# ESIMA_E-Meter_CPU.net
KiCad netlist of a schematic drawn in Altium Designer
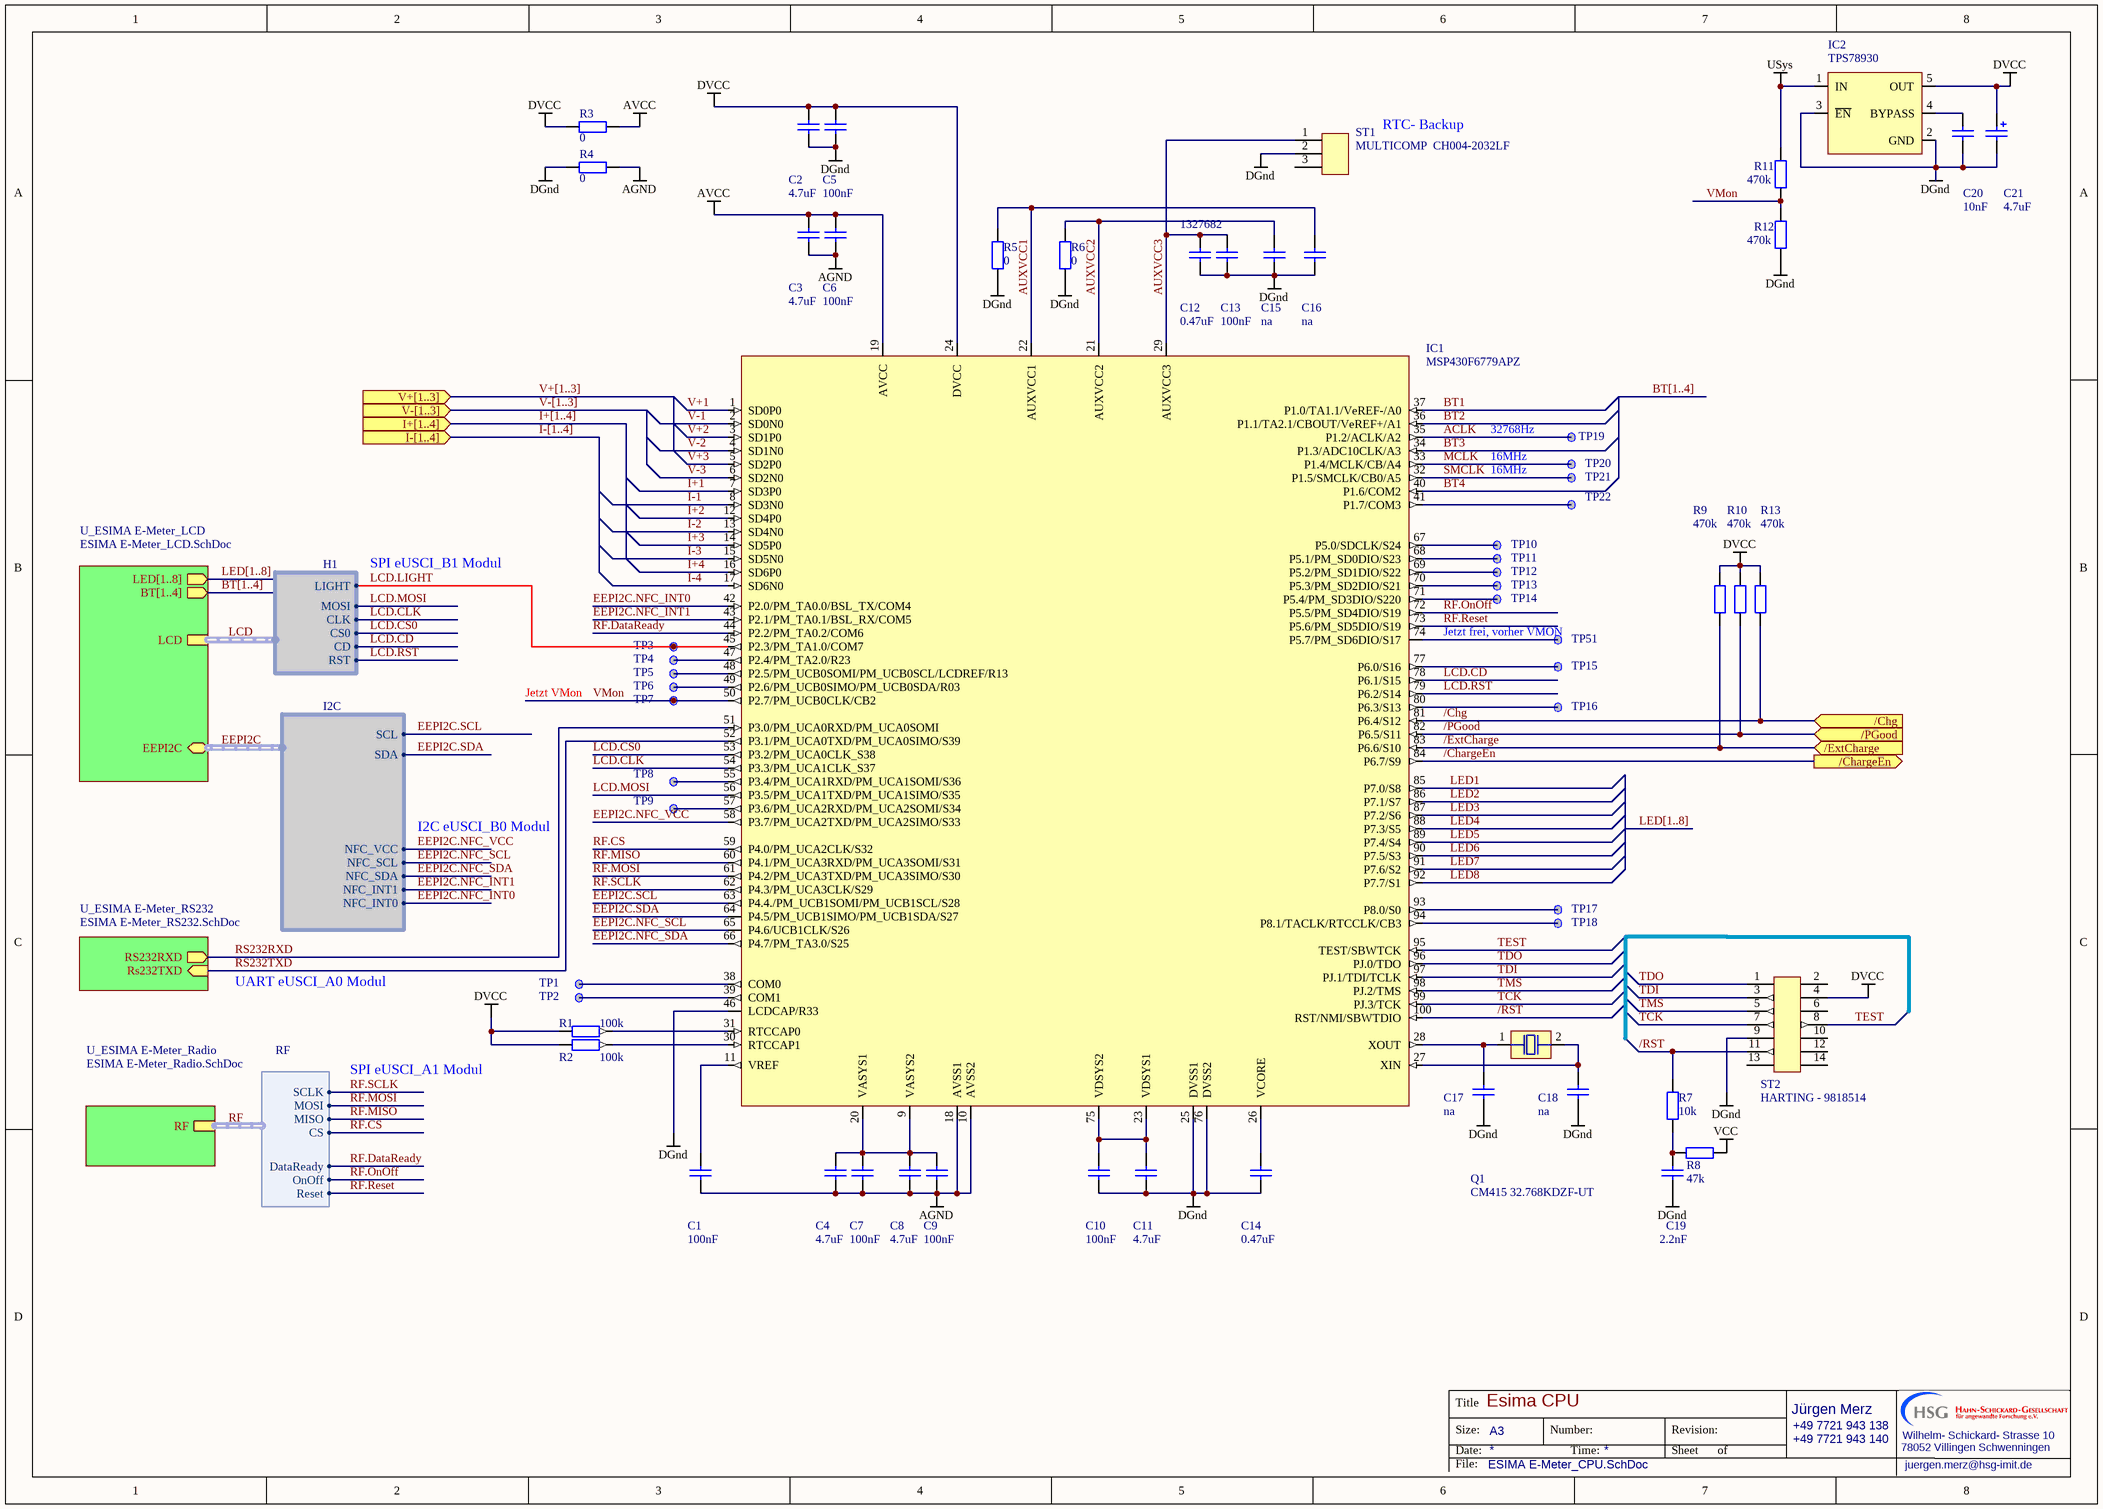
[diagram p0: ESIMA E-Meter_CPU.SchDoc]

(export (version "E")
  (design (tool "Eeschema 10.0.6"))
  (components
    (comp (ref "C1")
      (value "100nF")
      (footprint "CAPC1608N")
      (description "CAPC1608 (C0603)")
      (libsource (lib "JM_Kondensatoren") (part "CAPC1608 (C0603)"))
    )
    (comp (ref "C2")
      (value "4.7uF")
      (footprint "CAPC1608N")
      (description "CAPC1608 (C0603)")
      (libsource (lib "JM_Kondensatoren") (part "CAPC1608 (C0603)"))
    )
    (comp (ref "C3")
      (value "4.7uF")
      (footprint "CAPC1608N")
      (description "CAPC1608 (C0603)")
      (libsource (lib "JM_Kondensatoren") (part "CAPC1608 (C0603)"))
    )
    (comp (ref "C4")
      (value "4.7uF")
      (footprint "CAPC1608N")
      (description "CAPC1608 (C0603)")
      (libsource (lib "JM_Kondensatoren") (part "CAPC1608 (C0603)"))
    )
    (comp (ref "C5")
      (value "100nF")
      (footprint "CAPC1608N")
      (description "CAPC1608 (C0603)")
      (libsource (lib "JM_Kondensatoren") (part "CAPC1608 (C0603)"))
    )
    (comp (ref "C6")
      (value "100nF")
      (footprint "CAPC1608N")
      (description "CAPC1608 (C0603)")
      (libsource (lib "JM_Kondensatoren") (part "CAPC1608 (C0603)"))
    )
    (comp (ref "C7")
      (value "100nF")
      (footprint "CAPC1608N")
      (description "CAPC1608 (C0603)")
      (libsource (lib "JM_Kondensatoren") (part "CAPC1608 (C0603)"))
    )
    (comp (ref "C8")
      (value "4.7uF")
      (footprint "CAPC1608N")
      (description "CAPC1608 (C0603)")
      (libsource (lib "JM_Kondensatoren") (part "CAPC1608 (C0603)"))
    )
    (comp (ref "C9")
      (value "100nF")
      (footprint "CAPC1608N")
      (description "CAPC1608 (C0603)")
      (libsource (lib "JM_Kondensatoren") (part "CAPC1608 (C0603)"))
    )
    (comp (ref "C10")
      (value "100nF")
      (footprint "CAPC1608N")
      (description "CAPC1608 (C0603)")
      (libsource (lib "JM_Kondensatoren") (part "CAPC1608 (C0603)"))
    )
    (comp (ref "C11")
      (value "4.7uF")
      (footprint "CAPC1608N")
      (description "CAPC1608 (C0603)")
      (libsource (lib "JM_Kondensatoren") (part "CAPC1608 (C0603)"))
    )
    (comp (ref "C12")
      (value "0.47uF")
      (footprint "CAPC1608N")
      (description "CAPC1608 (C0603)")
      (fields (field (name "SUPPLIER PART NUMBER 1") "1327682"))
      (libsource (lib "JM_Kondensatoren") (part "CAPC1608 (C0603)"))
    )
    (comp (ref "C13")
      (value "100nF")
      (footprint "CAPC1608N")
      (description "CAPC1608 (C0603)")
      (libsource (lib "JM_Kondensatoren") (part "CAPC1608 (C0603)"))
    )
    (comp (ref "C14")
      (value "0.47uF")
      (footprint "CAPC1608N")
      (description "CAPC1608 (C0603)")
      (libsource (lib "JM_Kondensatoren") (part "CAPC1608 (C0603)"))
    )
    (comp (ref "C15")
      (value "na")
      (footprint "CAPC1608N")
      (description "CAPC1608 (C0603)")
      (libsource (lib "JM_Kondensatoren") (part "CAPC1608 (C0603)"))
    )
    (comp (ref "C16")
      (value "na")
      (footprint "CAPC1608N")
      (description "CAPC1608 (C0603)")
      (libsource (lib "JM_Kondensatoren") (part "CAPC1608 (C0603)"))
    )
    (comp (ref "C17")
      (value "na")
      (footprint "CAPC1608N")
      (description "CAPC1608 (C0603)")
      (libsource (lib "JM_Kondensatoren") (part "CAPC1608 (C0603)"))
    )
    (comp (ref "C18")
      (value "na")
      (footprint "CAPC1608N")
      (description "CAPC1608 (C0603)")
      (libsource (lib "JM_Kondensatoren") (part "CAPC1608 (C0603)"))
    )
    (comp (ref "C19")
      (value "2.2nF")
      (footprint "CAPC1608N")
      (description "CAPC1608 (C0603)")
      (libsource (lib "JM_Kondensatoren") (part "CAPC1608 (C0603)"))
    )
    (comp (ref "C20")
      (value "10nF")
      (footprint "CAPC1608N")
      (description "CAPC1608 (C0603)")
      (libsource (lib "JM_Kondensatoren") (part "CAPC1608 (C0603)"))
    )
    (comp (ref "C21")
      (value "4.7uF")
      (footprint "Cap Tant Pol Form B")
      (libsource (lib "JM_Kondensatoren") (part "Cap Tant Pol Form B"))
    )
    (comp (ref "IC1")
      (value "MSP430F6779APZ")
      (footprint "TI-PZ100_N")
      (description "Mikroprozessor 16bit Polyphase Metering")
      (libsource (lib "JM_Halbleiter") (part "MSP430F6779AIPZ"))
    )
    (comp (ref "IC2")
      (value "TPS78930")
      (footprint "TI-DBV5 (SOT23-5)")
      (description "Voltageregulator low Current")
      (libsource (lib "HSG-IMIT_JuergenMerz") (part "TPS78930"))
    )
    (comp (ref "Q1")
      (value "CM415 32.768KDZF-UT")
      (footprint "Quarz 2 Pin 4.1mm * 1.5mm")
      (description "Quarz 2 Pin 4.1mm * 1.5mm")
      (libsource (lib "JM_Kondensatoren") (part "Quarz 2 Pin 4.1mm * 1.5mm"))
    )
    (comp (ref "R1")
      (value "100k")
      (footprint "RESC1608N")
      (description "RESC1608 (R0603)")
      (libsource (lib "JM_Widerstaende") (part "RESC1608 (R0603)"))
    )
    (comp (ref "R2")
      (value "100k")
      (footprint "RESC1608N")
      (description "RESC1608 (R0603)")
      (libsource (lib "JM_Widerstaende") (part "RESC1608 (R0603)"))
    )
    (comp (ref "R3")
      (value "0")
      (footprint "RESC2012N")
      (description "RESC2012N (R0805)")
      (libsource (lib "JM_Widerstaende") (part "RESC2012N (R0805)"))
    )
    (comp (ref "R4")
      (value "0")
      (footprint "RESC2012N")
      (description "RESC2012N (R0805)")
      (libsource (lib "JM_Widerstaende") (part "RESC2012N (R0805)"))
    )
    (comp (ref "R5")
      (value "0")
      (footprint "RESC1608N")
      (description "RESC1608 (R0603)")
      (libsource (lib "") (part "RESC1608 (R0603)_1"))
    )
    (comp (ref "R6")
      (value "0")
      (footprint "RESC1608N")
      (description "RESC1608 (R0603)")
      (libsource (lib "") (part "RESC1608 (R0603)_1"))
    )
    (comp (ref "R7")
      (value "10k")
      (footprint "RESC1608N")
      (description "RESC1608 (R0603)")
      (libsource (lib "") (part "RESC1608 (R0603)_2"))
    )
    (comp (ref "R8")
      (value "47k")
      (footprint "RESC1608N")
      (description "RESC1608 (R0603)")
      (libsource (lib "JM_Widerstaende") (part "RESC1608 (R0603)"))
    )
    (comp (ref "R9")
      (value "470k")
      (footprint "RESC1608N")
      (description "RESC1608 (R0603)")
      (libsource (lib "JM_Widerstaende") (part "RESC1608 (R0603)"))
    )
    (comp (ref "R10")
      (value "470k")
      (footprint "RESC1608N")
      (description "RESC1608 (R0603)")
      (libsource (lib "JM_Widerstaende") (part "RESC1608 (R0603)"))
    )
    (comp (ref "R11")
      (value "470k")
      (footprint "RESC1608N")
      (description "RESC1608 (R0603)")
      (libsource (lib "") (part "RESC1608 (R0603)_1"))
    )
    (comp (ref "R12")
      (value "470k")
      (footprint "RESC1608N")
      (description "RESC1608 (R0603)")
      (libsource (lib "") (part "RESC1608 (R0603)_1"))
    )
    (comp (ref "R13")
      (value "470k")
      (footprint "RESC1608N")
      (description "RESC1608 (R0603)")
      (libsource (lib "JM_Widerstaende") (part "RESC1608 (R0603)"))
    )
    (comp (ref "ST1")
      (value "MULTICOMP  CH004-2032LF")
      (footprint "MULTICOMP  CH004-2032LF")
      (description "Stecker 3Pol universal")
      (libsource (lib "HSG-IMIT_JuergenMerz") (part "Stecker 3Pol universal"))
    )
    (comp (ref "ST2")
      (value "HARTING - 9818514")
      (footprint "HARTING -09 18 514 7324")
      (description "Messerleiste Gerade 14Pol")
      (libsource (lib "JM_Elektromechanik") (part "HARTING - 9818514"))
    )
    (comp (ref "TP1")
      (value "Testpoint 1mm")
      (footprint "Testpoint 1mm")
      (libsource (lib "HSG-IMIT_JuergenMerz") (part "Tespoint 1mm"))
    )
    (comp (ref "TP2")
      (value "Testpoint 1mm")
      (footprint "Testpoint 1mm")
      (libsource (lib "HSG-IMIT_JuergenMerz") (part "Tespoint 1mm"))
    )
    (comp (ref "TP3")
      (value "Testpoint 1mm")
      (footprint "Testpoint 1mm")
      (libsource (lib "HSG-IMIT_JuergenMerz") (part "Tespoint 1mm"))
    )
    (comp (ref "TP4")
      (value "Testpoint 1mm")
      (footprint "Testpoint 1mm")
      (libsource (lib "HSG-IMIT_JuergenMerz") (part "Tespoint 1mm"))
    )
    (comp (ref "TP5")
      (value "Testpoint 1mm")
      (footprint "Testpoint 1mm")
      (libsource (lib "HSG-IMIT_JuergenMerz") (part "Tespoint 1mm"))
    )
    (comp (ref "TP6")
      (value "Testpoint 1mm")
      (footprint "Testpoint 1mm")
      (libsource (lib "HSG-IMIT_JuergenMerz") (part "Tespoint 1mm"))
    )
    (comp (ref "TP7")
      (value "Testpoint 1mm")
      (footprint "Testpoint 1mm")
      (libsource (lib "HSG-IMIT_JuergenMerz") (part "Tespoint 1mm"))
    )
    (comp (ref "TP8")
      (value "Testpoint 1mm")
      (footprint "Testpoint 1mm")
      (libsource (lib "HSG-IMIT_JuergenMerz") (part "Tespoint 1mm"))
    )
    (comp (ref "TP9")
      (value "Testpoint 1mm")
      (footprint "Testpoint 1mm")
      (libsource (lib "HSG-IMIT_JuergenMerz") (part "Tespoint 1mm"))
    )
    (comp (ref "TP10")
      (value "Testpoint 1mm")
      (footprint "Testpoint 1mm")
      (libsource (lib "HSG-IMIT_JuergenMerz") (part "Tespoint 1mm"))
    )
    (comp (ref "TP11")
      (value "Testpoint 1mm")
      (footprint "Testpoint 1mm")
      (libsource (lib "HSG-IMIT_JuergenMerz") (part "Tespoint 1mm"))
    )
    (comp (ref "TP12")
      (value "Testpoint 1mm")
      (footprint "Testpoint 1mm")
      (libsource (lib "HSG-IMIT_JuergenMerz") (part "Tespoint 1mm"))
    )
    (comp (ref "TP13")
      (value "Testpoint 1mm")
      (footprint "Testpoint 1mm")
      (libsource (lib "HSG-IMIT_JuergenMerz") (part "Tespoint 1mm"))
    )
    (comp (ref "TP14")
      (value "Testpoint 1mm")
      (footprint "Testpoint 1mm")
      (libsource (lib "HSG-IMIT_JuergenMerz") (part "Tespoint 1mm"))
    )
    (comp (ref "TP15")
      (value "Testpoint 1mm")
      (footprint "Testpoint 1mm")
      (libsource (lib "HSG-IMIT_JuergenMerz") (part "Tespoint 1mm"))
    )
    (comp (ref "TP16")
      (value "Testpoint 1mm")
      (footprint "Testpoint 1mm")
      (libsource (lib "HSG-IMIT_JuergenMerz") (part "Tespoint 1mm"))
    )
    (comp (ref "TP17")
      (value "Testpoint 1mm")
      (footprint "Testpoint 1mm")
      (libsource (lib "HSG-IMIT_JuergenMerz") (part "Tespoint 1mm"))
    )
    (comp (ref "TP18")
      (value "Testpoint 1mm")
      (footprint "Testpoint 1mm")
      (libsource (lib "HSG-IMIT_JuergenMerz") (part "Tespoint 1mm"))
    )
    (comp (ref "TP19")
      (value "Testpoint 1mm")
      (footprint "Testpoint 1mm")
      (libsource (lib "HSG-IMIT_JuergenMerz") (part "Tespoint 1mm"))
    )
    (comp (ref "TP20")
      (value "Testpoint 1mm")
      (footprint "Testpoint 1mm")
      (libsource (lib "HSG-IMIT_JuergenMerz") (part "Tespoint 1mm"))
    )
    (comp (ref "TP21")
      (value "Testpoint 1mm")
      (footprint "Testpoint 1mm")
      (libsource (lib "HSG-IMIT_JuergenMerz") (part "Tespoint 1mm"))
    )
    (comp (ref "TP22")
      (value "Testpoint 1mm")
      (footprint "Testpoint 1mm")
      (libsource (lib "HSG-IMIT_JuergenMerz") (part "Tespoint 1mm"))
    )
    (comp (ref "TP51")
      (value "Testpoint 1mm")
      (footprint "Testpoint 1mm")
      (libsource (lib "HSG-IMIT_JuergenMerz") (part "Tespoint 1mm"))
    )
  )
  (nets
    (net (code "4") (name "/ACLK") (class "Default")
      (node (ref "IC1") (pin "35") (pinfunction "P1.2/ACLK/A2_35") (pintype "output"))
      (node (ref "TP19") (pin "1") (pintype "passive"))
    )
    (net (code "5") (name "/AUXVCC1") (class "Default")
      (node (ref "C16") (pin "2") (pinfunction "2_2") (pintype "passive"))
      (node (ref "IC1") (pin "22") (pinfunction "AUXVCC1_22") (pintype "power_in"))
      (node (ref "R5") (pin "2") (pinfunction "2_2") (pintype "passive"))
    )
    (net (code "6") (name "/AUXVCC2") (class "Default")
      (node (ref "C15") (pin "2") (pinfunction "2_2") (pintype "passive"))
      (node (ref "IC1") (pin "21") (pinfunction "AUXVCC2_21") (pintype "power_in"))
      (node (ref "R6") (pin "2") (pinfunction "2_2") (pintype "passive"))
    )
    (net (code "7") (name "/AUXVCC3") (class "Default")
      (node (ref "C12") (pin "2") (pinfunction "2_2") (pintype "passive"))
      (node (ref "C13") (pin "2") (pinfunction "2_2") (pintype "passive"))
      (node (ref "IC1") (pin "29") (pinfunction "AUXVCC3_29") (pintype "power_in"))
      (node (ref "ST1") (pin "1") (pinfunction "1_1") (pintype "passive"))
    )
    (net (code "8") (name "/BT1") (class "Default")
      (node (ref "IC1") (pin "37") (pinfunction "P1.0/TA1.1/VeREF-/A0_37") (pintype "input"))
    )
    (net (code "9") (name "/BT2") (class "Default")
      (node (ref "IC1") (pin "36") (pinfunction "P1.1/TA2.1/CBOUT/VeREF+/A1_36") (pintype "input"))
    )
    (net (code "10") (name "/BT3") (class "Default")
      (node (ref "IC1") (pin "34") (pinfunction "P1.3/ADC10CLK/A3_34") (pintype "input"))
    )
    (net (code "11") (name "/BT4") (class "Default")
      (node (ref "IC1") (pin "40") (pinfunction "P1.6/COM2_40") (pintype "input"))
    )
    (net (code "13") (name "/EEPI2C.NFC_INT0") (class "Default")
      (node (ref "IC1") (pin "42") (pinfunction "P2.0/PM_TA0.0/BSL_TX/COM4_42") (pintype "input"))
    )
    (net (code "14") (name "/EEPI2C.NFC_INT1") (class "Default")
      (node (ref "IC1") (pin "43") (pinfunction "P2.1/PM_TA0.1/BSL_RX/COM5_43") (pintype "input"))
    )
    (net (code "15") (name "/EEPI2C.NFC_SCL") (class "Default")
      (node (ref "IC1") (pin "65") (pinfunction "P4.6/UCB1CLK/S26_65") (pintype "open_collector"))
    )
    (net (code "16") (name "/EEPI2C.NFC_SDA") (class "Default")
      (node (ref "IC1") (pin "66") (pinfunction "P4.7/PM_TA3.0/S25_66") (pintype "output"))
    )
    (net (code "17") (name "/EEPI2C.NFC_VCC") (class "Default")
      (node (ref "IC1") (pin "58") (pinfunction "P3.7/PM_UCA2TXD/PM_UCA2SIMO/S33_58") (pintype "output"))
    )
    (net (code "18") (name "/EEPI2C.SCL") (class "Default")
      (node (ref "IC1") (pin "63") (pinfunction "P4.4./PM_UCB1SOMI/PM_UCB1SCL/S28_63") (pintype "output"))
    )
    (net (code "19") (name "/EEPI2C.SDA") (class "Default")
      (node (ref "IC1") (pin "64") (pinfunction "P4.5/PM_UCB1SIMO/PM_UCB1SDA/S27_64") (pintype "open_collector"))
    )
    (net (code "21") (name "/I+1") (class "Default")
      (node (ref "IC1") (pin "7") (pinfunction "SD3P0_7") (pintype "input"))
    )
    (net (code "22") (name "/I+2") (class "Default")
      (node (ref "IC1") (pin "12") (pinfunction "SD4P0_12") (pintype "input"))
    )
    (net (code "23") (name "/I+3") (class "Default")
      (node (ref "IC1") (pin "14") (pinfunction "SD5P0_14") (pintype "input"))
    )
    (net (code "24") (name "/I+4") (class "Default")
      (node (ref "IC1") (pin "16") (pinfunction "SD6P0_16") (pintype "input"))
    )
    (net (code "26") (name "/I-1") (class "Default")
      (node (ref "IC1") (pin "8") (pinfunction "SD3N0_8") (pintype "input"))
    )
    (net (code "27") (name "/I-2") (class "Default")
      (node (ref "IC1") (pin "13") (pinfunction "SD4N0_13") (pintype "input"))
    )
    (net (code "28") (name "/I-3") (class "Default")
      (node (ref "IC1") (pin "15") (pinfunction "SD5N0_15") (pintype "input"))
    )
    (net (code "29") (name "/I-4") (class "Default")
      (node (ref "IC1") (pin "17") (pinfunction "SD6N0_17") (pintype "input"))
    )
    (net (code "31") (name "/LCD.CD") (class "Default")
      (node (ref "IC1") (pin "78") (pinfunction "P6.1/S15_78") (pintype "output"))
    )
    (net (code "32") (name "/LCD.CLK") (class "Default")
      (node (ref "IC1") (pin "54") (pinfunction "P3.3/PM_UCA1CLK_S37_54") (pintype "output"))
    )
    (net (code "33") (name "/LCD.CS0") (class "Default")
      (node (ref "IC1") (pin "53") (pinfunction "P3.2/PM_UCA0CLK_S38_53") (pintype "output"))
    )
    (net (code "34") (name "/LCD.LIGHT") (class "Default")
      (node (ref "IC1") (pin "45") (pinfunction "P2.3/PM_TA1.0/COM7_45") (pintype "output"))
      (node (ref "TP3") (pin "1") (pintype "passive"))
    )
    (net (code "35") (name "/LCD.MOSI") (class "Default")
      (node (ref "IC1") (pin "56") (pinfunction "P3.5/PM_UCA1TXD/PM_UCA1SIMO/S35_56") (pintype "output"))
    )
    (net (code "36") (name "/LCD.RST") (class "Default")
      (node (ref "IC1") (pin "79") (pinfunction "P6.2/S14_79") (pintype "output"))
    )
    (net (code "37") (name "/LED1") (class "Default")
      (node (ref "IC1") (pin "85") (pinfunction "P7.0/S8_85") (pintype "output"))
    )
    (net (code "38") (name "/LED2") (class "Default")
      (node (ref "IC1") (pin "86") (pinfunction "P7.1/S7_86") (pintype "output"))
    )
    (net (code "39") (name "/LED3") (class "Default")
      (node (ref "IC1") (pin "87") (pinfunction "P7.2/S6_87") (pintype "output"))
    )
    (net (code "40") (name "/LED4") (class "Default")
      (node (ref "IC1") (pin "88") (pinfunction "P7.3/S5_88") (pintype "output"))
    )
    (net (code "41") (name "/LED5") (class "Default")
      (node (ref "IC1") (pin "89") (pinfunction "P7.4/S4_89") (pintype "output"))
    )
    (net (code "42") (name "/LED6") (class "Default")
      (node (ref "IC1") (pin "90") (pinfunction "P7.5/S3_90") (pintype "output"))
    )
    (net (code "43") (name "/LED7") (class "Default")
      (node (ref "IC1") (pin "91") (pinfunction "P7.6/S2_91") (pintype "output"))
    )
    (net (code "44") (name "/LED8") (class "Default")
      (node (ref "IC1") (pin "92") (pinfunction "P7.7/S1_92") (pintype "output"))
    )
    (net (code "46") (name "/MCLK") (class "Default")
      (node (ref "IC1") (pin "33") (pinfunction "P1.4/MCLK/CB/A4_33") (pintype "output"))
      (node (ref "TP20") (pin "1") (pintype "passive"))
    )
    (net (code "47") (name "/RF.CS") (class "Default")
      (node (ref "IC1") (pin "59") (pinfunction "P4.0/PM_UCA2CLK/S32_59") (pintype "output"))
    )
    (net (code "48") (name "/RF.DataReady") (class "Default")
      (node (ref "IC1") (pin "44") (pinfunction "P2.2/PM_TA0.2/COM6_44") (pintype "input"))
    )
    (net (code "49") (name "/RF.MISO") (class "Default")
      (node (ref "IC1") (pin "60") (pinfunction "P4.1/PM_UCA3RXD/PM_UCA3SOMI/S31_60") (pintype "output"))
    )
    (net (code "50") (name "/RF.MOSI") (class "Default")
      (node (ref "IC1") (pin "61") (pinfunction "P4.2/PM_UCA3TXD/PM_UCA3SIMO/S30_61") (pintype "output"))
    )
    (net (code "51") (name "/RF.OnOff") (class "Default")
      (node (ref "IC1") (pin "72") (pinfunction "P5.5/PM_SD4DIO/S19_72") (pintype "output"))
    )
    (net (code "52") (name "/RF.Reset") (class "Default")
      (node (ref "IC1") (pin "73") (pinfunction "P5.6/PM_SD5DIO/S19_73") (pintype "output"))
    )
    (net (code "53") (name "/RF.SCLK") (class "Default")
      (node (ref "IC1") (pin "62") (pinfunction "P4.3/PM_UCA3CLK/S29_62") (pintype "output"))
    )
    (net (code "55") (name "/RS232RXD") (class "Default")
      (node (ref "IC1") (pin "51") (pinfunction "P3.0/PM_UCA0RXD/PM_UCA0SOMI_51") (pintype "input"))
    )
    (net (code "56") (name "/RS232TXD") (class "Default")
      (node (ref "IC1") (pin "52") (pinfunction "P3.1/PM_UCA0TXD/PM_UCA0SIMO/S39_52") (pintype "output"))
    )
    (net (code "57") (name "/SMCLK") (class "Default")
      (node (ref "IC1") (pin "32") (pinfunction "P1.5/SMCLK/CB0/A5_32") (pintype "output"))
      (node (ref "TP21") (pin "1") (pintype "passive"))
    )
    (net (code "58") (name "/TCK") (class "Default")
      (node (ref "IC1") (pin "99") (pinfunction "PJ.3/TCK_99") (pintype "input"))
      (node (ref "ST2") (pin "7") (pinfunction "7_7") (pintype "output"))
    )
    (net (code "59") (name "/TDI") (class "Default")
      (node (ref "IC1") (pin "97") (pinfunction "PJ.1/TDI/TCLK_97") (pintype "input"))
      (node (ref "ST2") (pin "3") (pinfunction "3_3") (pintype "output"))
    )
    (net (code "60") (name "/TDO") (class "Default")
      (node (ref "IC1") (pin "96") (pinfunction "PJ.0/TDO_96") (pintype "output"))
      (node (ref "ST2") (pin "1") (pinfunction "1_1") (pintype "passive"))
    )
    (net (code "61") (name "/TEST") (class "Default")
      (node (ref "IC1") (pin "95") (pinfunction "TEST/SBWTCK_95") (pintype "input"))
      (node (ref "ST2") (pin "8") (pinfunction "8_8") (pintype "output"))
    )
    (net (code "62") (name "/TMS") (class "Default")
      (node (ref "IC1") (pin "98") (pinfunction "PJ.2/TMS_98") (pintype "input"))
      (node (ref "ST2") (pin "5") (pinfunction "5_5") (pintype "output"))
    )
    (net (code "63") (name "/V+1") (class "Default")
      (node (ref "IC1") (pin "1") (pinfunction "SD0P0_1") (pintype "input"))
    )
    (net (code "64") (name "/V+2") (class "Default")
      (node (ref "IC1") (pin "3") (pinfunction "SD1P0_3") (pintype "input"))
    )
    (net (code "65") (name "/V+3") (class "Default")
      (node (ref "IC1") (pin "5") (pinfunction "SD2P0_5") (pintype "input"))
    )
    (net (code "67") (name "/V-1") (class "Default")
      (node (ref "IC1") (pin "2") (pinfunction "SD0N0_2") (pintype "input"))
    )
    (net (code "68") (name "/V-2") (class "Default")
      (node (ref "IC1") (pin "4") (pinfunction "SD1N0_4") (pintype "input"))
    )
    (net (code "69") (name "/V-3") (class "Default")
      (node (ref "IC1") (pin "6") (pinfunction "SD2N0_6") (pintype "input"))
    )
    (net (code "71") (name "/VMon") (class "Default")
      (node (ref "IC1") (pin "50") (pinfunction "P2.7/PM_UCB0CLK/CB2_50") (pintype "output"))
      (node (ref "R11") (pin "1") (pinfunction "1_1") (pintype "passive"))
      (node (ref "R12") (pin "2") (pinfunction "2_2") (pintype "passive"))
      (node (ref "TP7") (pin "1") (pintype "passive"))
    )
    (net (code "74") (name "/{slash}ChargeEn") (class "Default")
      (node (ref "IC1") (pin "84") (pinfunction "P6.7/S9_84") (pintype "output"))
    )
    (net (code "75") (name "/{slash}Chg") (class "Default")
      (node (ref "IC1") (pin "81") (pinfunction "P6.4/S12_81") (pintype "input"))
      (node (ref "R13") (pin "2") (pinfunction "2_2") (pintype "passive"))
    )
    (net (code "76") (name "/{slash}ExtCharge") (class "Default")
      (node (ref "IC1") (pin "83") (pinfunction "P6.6/S10_83") (pintype "input"))
      (node (ref "R9") (pin "2") (pinfunction "2_2") (pintype "passive"))
    )
    (net (code "77") (name "/{slash}PGood") (class "Default")
      (node (ref "IC1") (pin "82") (pinfunction "P6.5/S11_82") (pintype "input"))
      (node (ref "R10") (pin "2") (pinfunction "2_2") (pintype "passive"))
    )
    (net (code "78") (name "/{slash}RST") (class "Default")
      (node (ref "IC1") (pin "100") (pinfunction "RST/NMI/SBWTDIO_100") (pintype "input"))
      (node (ref "R7") (pin "1") (pinfunction "1_1") (pintype "passive"))
      (node (ref "ST2") (pin "11") (pinfunction "11_11") (pintype "output"))
    )
    (net (code "79") (name "AGND") (class "Default")
      (node (ref "C1") (pin "1") (pinfunction "1_1") (pintype "passive"))
      (node (ref "C3") (pin "1") (pinfunction "1_1") (pintype "passive"))
      (node (ref "C4") (pin "1") (pinfunction "1_1") (pintype "passive"))
      (node (ref "C6") (pin "1") (pinfunction "1_1") (pintype "passive"))
      (node (ref "C7") (pin "1") (pinfunction "1_1") (pintype "passive"))
      (node (ref "C8") (pin "1") (pinfunction "1_1") (pintype "passive"))
      (node (ref "C9") (pin "1") (pinfunction "1_1") (pintype "passive"))
      (node (ref "IC1") (pin "10") (pinfunction "AVSS2_10") (pintype "power_in"))
      (node (ref "IC1") (pin "18") (pinfunction "AVSS1_18") (pintype "power_in"))
      (node (ref "R4") (pin "1") (pinfunction "1_1") (pintype "passive"))
    )
    (net (code "80") (name "AVCC") (class "Default")
      (node (ref "C3") (pin "2") (pinfunction "2_2") (pintype "passive"))
      (node (ref "C6") (pin "2") (pinfunction "2_2") (pintype "passive"))
      (node (ref "IC1") (pin "19") (pinfunction "AVCC_19") (pintype "power_in"))
      (node (ref "R3") (pin "1") (pinfunction "1_1") (pintype "passive"))
    )
    (net (code "81") (name "DGnd") (class "Default")
      (node (ref "C10") (pin "1") (pinfunction "1_1") (pintype "passive"))
      (node (ref "C11") (pin "1") (pinfunction "1_1") (pintype "passive"))
      (node (ref "C12") (pin "1") (pinfunction "1_1") (pintype "passive"))
      (node (ref "C13") (pin "1") (pinfunction "1_1") (pintype "passive"))
      (node (ref "C14") (pin "1") (pinfunction "1_1") (pintype "passive"))
      (node (ref "C15") (pin "1") (pinfunction "1_1") (pintype "passive"))
      (node (ref "C16") (pin "1") (pinfunction "1_1") (pintype "passive"))
      (node (ref "C17") (pin "1") (pinfunction "1_1") (pintype "passive"))
      (node (ref "C18") (pin "1") (pinfunction "1_1") (pintype "passive"))
      (node (ref "C19") (pin "1") (pinfunction "1_1") (pintype "passive"))
      (node (ref "C2") (pin "1") (pinfunction "1_1") (pintype "passive"))
      (node (ref "C20") (pin "1") (pinfunction "1_1") (pintype "passive"))
      (node (ref "C21") (pin "2") (pinfunction "2_2") (pintype "passive"))
      (node (ref "C5") (pin "1") (pinfunction "1_1") (pintype "passive"))
      (node (ref "IC1") (pin "25") (pinfunction "DVSS1_25") (pintype "power_in"))
      (node (ref "IC1") (pin "46") (pinfunction "LCDCAP/R33_46") (pintype "passive"))
      (node (ref "IC1") (pin "76") (pinfunction "DVSS2_76") (pintype "power_in"))
      (node (ref "IC2") (pin "2") (pinfunction "GND_2") (pintype "power_in"))
      (node (ref "IC2") (pin "3") (pinfunction "~{EN}_3") (pintype "passive"))
      (node (ref "R12") (pin "1") (pinfunction "1_1") (pintype "passive"))
      (node (ref "R4") (pin "2") (pinfunction "2_2") (pintype "passive"))
      (node (ref "R5") (pin "1") (pinfunction "1_1") (pintype "passive"))
      (node (ref "R6") (pin "1") (pinfunction "1_1") (pintype "passive"))
      (node (ref "ST1") (pin "2") (pinfunction "2_2") (pintype "passive"))
      (node (ref "ST2") (pin "9") (pinfunction "9_9") (pintype "passive"))
    )
    (net (code "82") (name "DVCC") (class "Default")
      (node (ref "C2") (pin "2") (pinfunction "2_2") (pintype "passive"))
      (node (ref "C21") (pin "1") (pinfunction "1_1") (pintype "passive"))
      (node (ref "C5") (pin "2") (pinfunction "2_2") (pintype "passive"))
      (node (ref "IC1") (pin "24") (pinfunction "DVCC_24") (pintype "power_in"))
      (node (ref "IC2") (pin "5") (pinfunction "OUT_5") (pintype "power_in"))
      (node (ref "R1") (pin "2") (pinfunction "2_2") (pintype "passive"))
      (node (ref "R10") (pin "1") (pinfunction "1_1") (pintype "passive"))
      (node (ref "R13") (pin "1") (pinfunction "1_1") (pintype "passive"))
      (node (ref "R2") (pin "2") (pinfunction "2_2") (pintype "passive"))
      (node (ref "R3") (pin "2") (pinfunction "2_2") (pintype "passive"))
      (node (ref "R9") (pin "1") (pinfunction "1_1") (pintype "passive"))
      (node (ref "ST2") (pin "4") (pinfunction "4_4") (pintype "passive"))
    )
    (net (code "83") (name "Net-(C19-Pad2)") (class "Default")
      (node (ref "C19") (pin "2") (pinfunction "2_2") (pintype "passive"))
      (node (ref "R7") (pin "2") (pinfunction "2_2") (pintype "passive"))
      (node (ref "R8") (pin "2") (pinfunction "2_2") (pintype "passive"))
    )
    (net (code "84") (name "Net-(IC1-COM0)") (class "Default")
      (node (ref "IC1") (pin "38") (pinfunction "COM0_38") (pintype "output"))
      (node (ref "TP1") (pin "1") (pintype "passive"))
    )
    (net (code "85") (name "Net-(IC1-COM1)") (class "Default")
      (node (ref "IC1") (pin "39") (pinfunction "COM1_39") (pintype "output"))
      (node (ref "TP2") (pin "1") (pintype "passive"))
    )
    (net (code "86") (name "Net-(IC1-P1.7{slash}COM3)") (class "Default")
      (node (ref "IC1") (pin "41") (pinfunction "P1.7/COM3_41") (pintype "output"))
      (node (ref "TP22") (pin "1") (pintype "passive"))
    )
    (net (code "87") (name "Net-(IC1-P2.4{slash}PM_TA2.0{slash}R23)") (class "Default")
      (node (ref "IC1") (pin "47") (pinfunction "P2.4/PM_TA2.0/R23_47") (pintype "output"))
      (node (ref "TP4") (pin "1") (pintype "passive"))
    )
    (net (code "88") (name "Net-(IC1-P2.5{slash}PM_UCB0SOMI{slash}PM_UCB0SCL{slash}LCDREF{slash}R13)") (class "Default")
      (node (ref "IC1") (pin "48") (pinfunction "P2.5/PM_UCB0SOMI/PM_UCB0SCL/LCDREF/R13_48") (pintype "output"))
      (node (ref "TP5") (pin "1") (pintype "passive"))
    )
    (net (code "89") (name "Net-(IC1-P2.6{slash}PM_UCB0SIMO{slash}PM_UCB0SDA{slash}R03)") (class "Default")
      (node (ref "IC1") (pin "49") (pinfunction "P2.6/PM_UCB0SIMO/PM_UCB0SDA/R03_49") (pintype "output"))
      (node (ref "TP6") (pin "1") (pintype "passive"))
    )
    (net (code "90") (name "Net-(IC1-P3.4{slash}PM_UCA1RXD{slash}PM_UCA1SOMI{slash}S36)") (class "Default")
      (node (ref "IC1") (pin "55") (pinfunction "P3.4/PM_UCA1RXD/PM_UCA1SOMI/S36_55") (pintype "output"))
      (node (ref "TP8") (pin "1") (pintype "passive"))
    )
    (net (code "91") (name "Net-(IC1-P3.6{slash}PM_UCA2RXD{slash}PM_UCA2SOMI{slash}S34)") (class "Default")
      (node (ref "IC1") (pin "57") (pinfunction "P3.6/PM_UCA2RXD/PM_UCA2SOMI/S34_57") (pintype "output"))
      (node (ref "TP9") (pin "1") (pintype "passive"))
    )
    (net (code "92") (name "Net-(IC1-P5.0{slash}SDCLK{slash}S24)") (class "Default")
      (node (ref "IC1") (pin "67") (pinfunction "P5.0/SDCLK/S24_67") (pintype "output"))
      (node (ref "TP10") (pin "1") (pintype "passive"))
    )
    (net (code "93") (name "Net-(IC1-P5.1{slash}PM_SD0DIO{slash}S23)") (class "Default")
      (node (ref "IC1") (pin "68") (pinfunction "P5.1/PM_SD0DIO/S23_68") (pintype "output"))
      (node (ref "TP11") (pin "1") (pintype "passive"))
    )
    (net (code "94") (name "Net-(IC1-P5.2{slash}PM_SD1DIO{slash}S22)") (class "Default")
      (node (ref "IC1") (pin "69") (pinfunction "P5.2/PM_SD1DIO/S22_69") (pintype "output"))
      (node (ref "TP12") (pin "1") (pintype "passive"))
    )
    (net (code "95") (name "Net-(IC1-P5.3{slash}PM_SD2DIO{slash}S21)") (class "Default")
      (node (ref "IC1") (pin "70") (pinfunction "P5.3/PM_SD2DIO/S21_70") (pintype "output"))
      (node (ref "TP13") (pin "1") (pintype "passive"))
    )
    (net (code "96") (name "Net-(IC1-P5.4{slash}PM_SD3DIO{slash}S220)") (class "Default")
      (node (ref "IC1") (pin "71") (pinfunction "P5.4/PM_SD3DIO/S220_71") (pintype "output"))
      (node (ref "TP14") (pin "1") (pintype "passive"))
    )
    (net (code "97") (name "Net-(IC1-P5.7{slash}PM_SD6DIO{slash}S17)") (class "Default")
      (node (ref "IC1") (pin "74") (pinfunction "P5.7/PM_SD6DIO/S17_74") (pintype "passive"))
      (node (ref "TP51") (pin "1") (pintype "passive"))
    )
    (net (code "98") (name "Net-(IC1-P6.0{slash}S16)") (class "Default")
      (node (ref "IC1") (pin "77") (pinfunction "P6.0/S16_77") (pintype "output"))
      (node (ref "TP15") (pin "1") (pintype "passive"))
    )
    (net (code "99") (name "Net-(IC1-P6.3{slash}S13)") (class "Default")
      (node (ref "IC1") (pin "80") (pinfunction "P6.3/S13_80") (pintype "output"))
      (node (ref "TP16") (pin "1") (pintype "passive"))
    )
    (net (code "100") (name "Net-(IC1-P8.0{slash}S0)") (class "Default")
      (node (ref "IC1") (pin "93") (pinfunction "P8.0/S0_93") (pintype "output"))
      (node (ref "TP17") (pin "1") (pintype "passive"))
    )
    (net (code "101") (name "Net-(IC1-P8.1{slash}TACLK{slash}RTCCLK{slash}CB3)") (class "Default")
      (node (ref "IC1") (pin "94") (pinfunction "P8.1/TACLK/RTCCLK/CB3_94") (pintype "output"))
      (node (ref "TP18") (pin "1") (pintype "passive"))
    )
    (net (code "102") (name "Net-(IC1-RTCCAP0)") (class "Default")
      (node (ref "IC1") (pin "31") (pinfunction "RTCCAP0_31") (pintype "input"))
      (node (ref "R1") (pin "1") (pinfunction "1_1") (pintype "passive"))
    )
    (net (code "103") (name "Net-(IC1-RTCCAP1)") (class "Default")
      (node (ref "IC1") (pin "30") (pinfunction "RTCCAP1_30") (pintype "input"))
      (node (ref "R2") (pin "1") (pinfunction "1_1") (pintype "passive"))
    )
    (net (code "104") (name "Net-(IC1-VASYS1)") (class "Default")
      (node (ref "C4") (pin "2") (pinfunction "2_2") (pintype "passive"))
      (node (ref "C7") (pin "2") (pinfunction "2_2") (pintype "passive"))
      (node (ref "C8") (pin "2") (pinfunction "2_2") (pintype "passive"))
      (node (ref "C9") (pin "2") (pinfunction "2_2") (pintype "passive"))
      (node (ref "IC1") (pin "20") (pinfunction "VASYS1_20") (pintype "power_in"))
      (node (ref "IC1") (pin "9") (pinfunction "VASYS2_9") (pintype "power_in"))
    )
    (net (code "105") (name "Net-(IC1-VCORE)") (class "Default")
      (node (ref "C14") (pin "2") (pinfunction "2_2") (pintype "passive"))
      (node (ref "IC1") (pin "26") (pinfunction "VCORE_26") (pintype "passive"))
    )
    (net (code "106") (name "Net-(IC1-VDSYS1)") (class "Default")
      (node (ref "C10") (pin "2") (pinfunction "2_2") (pintype "passive"))
      (node (ref "C11") (pin "2") (pinfunction "2_2") (pintype "passive"))
      (node (ref "IC1") (pin "23") (pinfunction "VDSYS1_23") (pintype "power_in"))
      (node (ref "IC1") (pin "75") (pinfunction "VDSYS2_75") (pintype "power_in"))
    )
    (net (code "107") (name "Net-(IC1-VREF)") (class "Default")
      (node (ref "C1") (pin "2") (pinfunction "2_2") (pintype "passive"))
      (node (ref "IC1") (pin "11") (pinfunction "VREF_11") (pintype "output"))
    )
    (net (code "108") (name "Net-(IC1-XIN)") (class "Default")
      (node (ref "C18") (pin "2") (pinfunction "2_2") (pintype "passive"))
      (node (ref "IC1") (pin "27") (pinfunction "XIN_27") (pintype "input"))
      (node (ref "Q1") (pin "2") (pinfunction "Out_2") (pintype "power_in"))
    )
    (net (code "109") (name "Net-(IC1-XOUT)") (class "Default")
      (node (ref "C17") (pin "2") (pinfunction "2_2") (pintype "passive"))
      (node (ref "IC1") (pin "28") (pinfunction "XOUT_28") (pintype "output"))
      (node (ref "Q1") (pin "1") (pinfunction "In_1") (pintype "passive"))
    )
    (net (code "110") (name "Net-(IC2-BYPASS)") (class "Default")
      (node (ref "C20") (pin "2") (pinfunction "2_2") (pintype "passive"))
      (node (ref "IC2") (pin "4") (pinfunction "BYPASS_4") (pintype "passive"))
    )
    (net (code "111") (name "USys") (class "Default")
      (node (ref "IC2") (pin "1") (pinfunction "IN_1") (pintype "power_in"))
      (node (ref "R11") (pin "2") (pinfunction "2_2") (pintype "passive"))
    )
    (net (code "112") (name "VCC") (class "Default")
      (node (ref "R8") (pin "1") (pinfunction "1_1") (pintype "passive"))
    )
    (net (code "113") (name "unconnected-(ST1-Pad3)") (class "Default")
      (node (ref "ST1") (pin "3") (pinfunction "3_3") (pintype "passive"))
    )
    (net (code "114") (name "unconnected-(ST2-Pad2)") (class "Default")
      (node (ref "ST2") (pin "2") (pinfunction "2_2") (pintype "passive"))
    )
    (net (code "115") (name "unconnected-(ST2-Pad6)") (class "Default")
      (node (ref "ST2") (pin "6") (pinfunction "6_6") (pintype "passive"))
    )
    (net (code "116") (name "unconnected-(ST2-Pad10)") (class "Default")
      (node (ref "ST2") (pin "10") (pinfunction "10_10") (pintype "passive"))
    )
    (net (code "117") (name "unconnected-(ST2-Pad12)") (class "Default")
      (node (ref "ST2") (pin "12") (pinfunction "12_12") (pintype "passive"))
    )
    (net (code "118") (name "unconnected-(ST2-Pad13)") (class "Default")
      (node (ref "ST2") (pin "13") (pinfunction "13_13") (pintype "passive"))
    )
    (net (code "119") (name "unconnected-(ST2-Pad14)") (class "Default")
      (node (ref "ST2") (pin "14") (pinfunction "14_14") (pintype "passive"))
    )
  )
)
